# ADC.net
KiCad netlist of a schematic drawn in Altium Designer
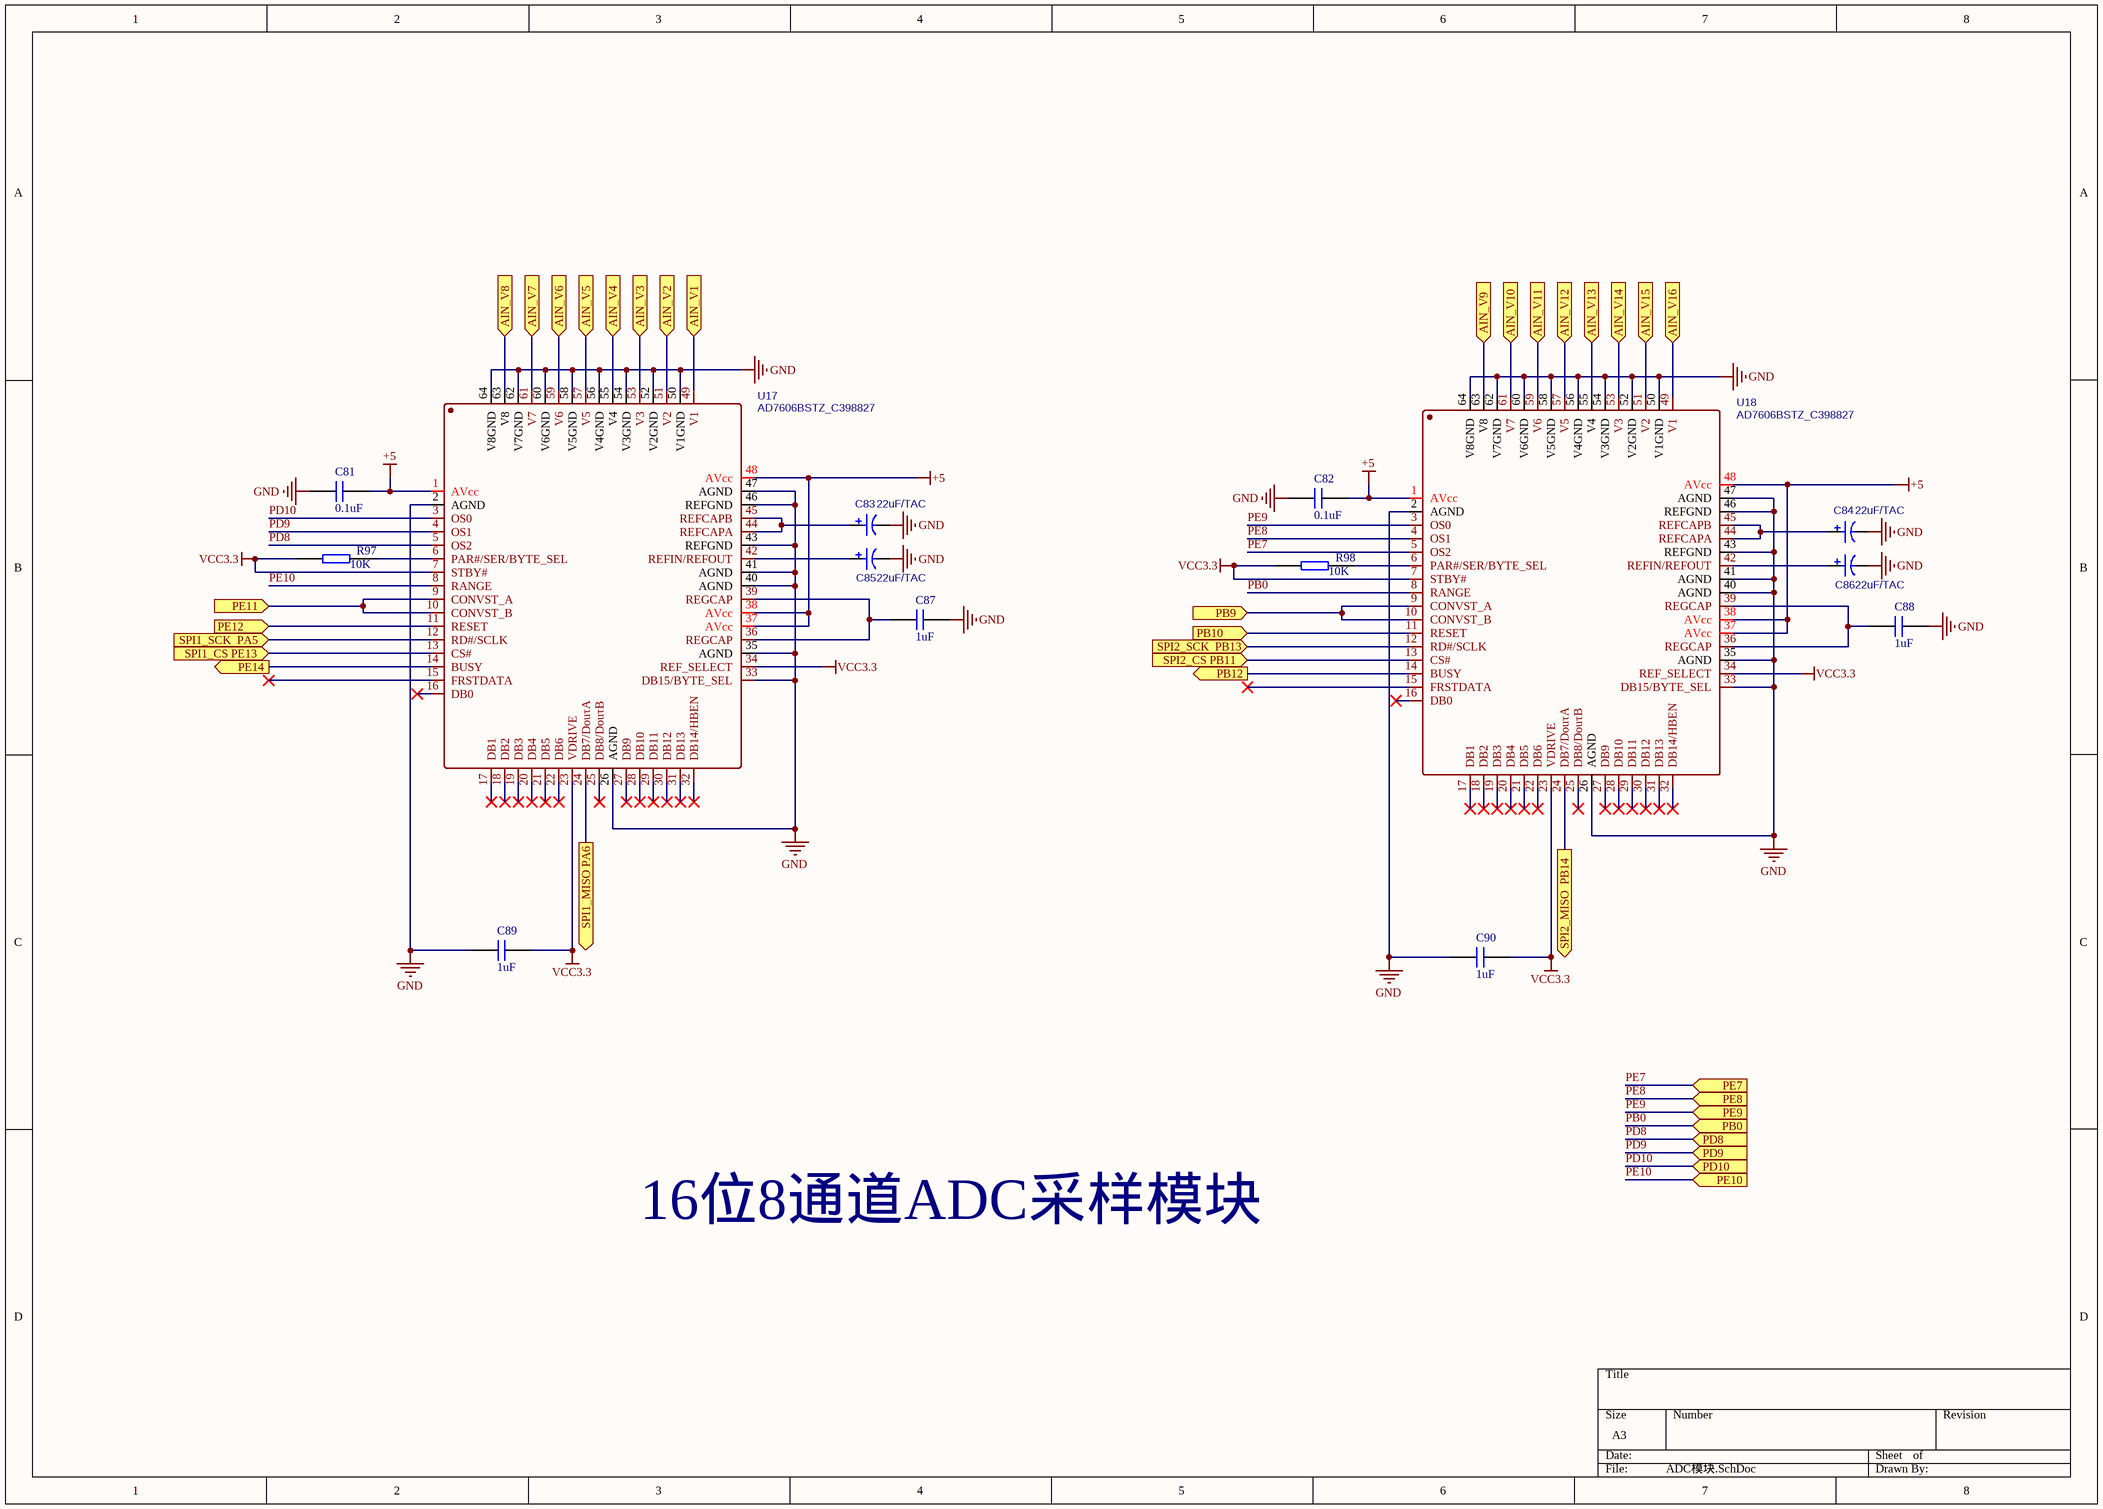
[diagram p0: ADC模块.SchDoc]

(export (version "E")
  (design (tool "Eeschema 10.0.6"))
  (components
    (comp (ref "C81")
      (value "0.1uF")
      (footprint "0805C")
      (description "普通电容")
      (libsource (lib "毕业设计") (part "CAP"))
    )
    (comp (ref "C82")
      (value "0.1uF")
      (footprint "0805C")
      (description "普通电容")
      (libsource (lib "毕业设计") (part "CAP"))
    )
    (comp (ref "C83")
      (value "22uF/TAC")
      (footprint "CASE-C_6032")
      (description "极性电解电容")
      (fields
        (field (name "BOM_MANUFACTURER PART") "Non - polar electrolytic capacitors10uf 100v")
        (field (name "BOM_SUPPLIER PART") "C56706")
      )
      (libsource (lib "毕业设计") (part "10uF"))
    )
    (comp (ref "C84")
      (value "22uF/TAC")
      (footprint "CASE-C_6032")
      (description "极性电解电容")
      (fields
        (field (name "BOM_MANUFACTURER PART") "Non - polar electrolytic capacitors10uf 100v")
        (field (name "BOM_SUPPLIER PART") "C56706")
      )
      (libsource (lib "毕业设计") (part "10uF"))
    )
    (comp (ref "C85")
      (value "22uF/TAC")
      (footprint "CASE-C_6032")
      (description "极性电解电容")
      (fields
        (field (name "BOM_MANUFACTURER PART") "Non - polar electrolytic capacitors10uf 100v")
        (field (name "BOM_SUPPLIER PART") "C56706")
      )
      (libsource (lib "毕业设计") (part "10uF"))
    )
    (comp (ref "C86")
      (value "22uF/TAC")
      (footprint "CASE-C_6032")
      (description "极性电解电容")
      (fields
        (field (name "BOM_MANUFACTURER PART") "Non - polar electrolytic capacitors10uf 100v")
        (field (name "BOM_SUPPLIER PART") "C56706")
      )
      (libsource (lib "毕业设计") (part "10uF"))
    )
    (comp (ref "C87")
      (value "1uF")
      (footprint "0805C")
      (description "普通电容")
      (libsource (lib "毕业设计") (part "CAP"))
    )
    (comp (ref "C88")
      (value "1uF")
      (footprint "0805C")
      (description "普通电容")
      (libsource (lib "毕业设计") (part "CAP"))
    )
    (comp (ref "C89")
      (value "1uF")
      (footprint "0805C")
      (description "普通电容")
      (libsource (lib "毕业设计") (part "CAP"))
    )
    (comp (ref "C90")
      (value "1uF")
      (footprint "0805C")
      (description "普通电容")
      (libsource (lib "毕业设计") (part "CAP"))
    )
    (comp (ref "R97")
      (value "10K")
      (footprint "0603R")
      (description "电阻模型")
      (libsource (lib "毕业设计") (part "RES"))
    )
    (comp (ref "R98")
      (value "10K")
      (footprint "0603R")
      (description "电阻模型")
      (libsource (lib "毕业设计") (part "RES"))
    )
    (comp (ref "U17")
      (value "AD7606BSTZ_C398827")
      (footprint "LQFP-64")
      (description "16位8路通道ADC")
      (fields
        (field (name "BOM_SUPPLIER PART") "C398827")
        (field (name "BOM_MANUFACTURER PART") "AD7606BSTZ")
        (field (name "CONTRIBUTOR") "LCSC")
      )
      (libsource (lib "毕业设计") (part "AD7606BSTZ_C398827"))
    )
    (comp (ref "U18")
      (value "AD7606BSTZ_C398827")
      (footprint "LQFP-64")
      (description "16位8路通道ADC")
      (fields
        (field (name "BOM_SUPPLIER PART") "C398827")
        (field (name "BOM_MANUFACTURER PART") "AD7606BSTZ")
        (field (name "CONTRIBUTOR") "LCSC")
      )
      (libsource (lib "毕业设计") (part "AD7606BSTZ_C398827"))
    )
  )
  (nets
    (net (code "1") (name "+5") (class "Default")
      (node (ref "C81") (pin "2") (pinfunction "2_2") (pintype "passive"))
      (node (ref "C82") (pin "2") (pinfunction "2_2") (pintype "passive"))
      (node (ref "U17") (pin "1") (pinfunction "AVcc_1") (pintype "passive"))
      (node (ref "U17") (pin "37") (pinfunction "AVcc_37") (pintype "passive"))
      (node (ref "U17") (pin "38") (pinfunction "AVcc_38") (pintype "passive"))
      (node (ref "U17") (pin "48") (pinfunction "AVcc_48") (pintype "passive"))
      (node (ref "U18") (pin "1") (pinfunction "AVcc_1") (pintype "passive"))
      (node (ref "U18") (pin "37") (pinfunction "AVcc_37") (pintype "passive"))
      (node (ref "U18") (pin "38") (pinfunction "AVcc_38") (pintype "passive"))
      (node (ref "U18") (pin "48") (pinfunction "AVcc_48") (pintype "passive"))
    )
    (net (code "2") (name "/AIN_V1") (class "Default")
      (node (ref "U17") (pin "49") (pinfunction "V1_49") (pintype "passive"))
    )
    (net (code "3") (name "/AIN_V2") (class "Default")
      (node (ref "U17") (pin "51") (pinfunction "V2_51") (pintype "passive"))
    )
    (net (code "4") (name "/AIN_V3") (class "Default")
      (node (ref "U17") (pin "53") (pinfunction "V3_53") (pintype "passive"))
    )
    (net (code "5") (name "/AIN_V4") (class "Default")
      (node (ref "U17") (pin "55") (pinfunction "V4_55") (pintype "passive"))
    )
    (net (code "6") (name "/AIN_V5") (class "Default")
      (node (ref "U17") (pin "57") (pinfunction "V5_57") (pintype "passive"))
    )
    (net (code "7") (name "/AIN_V6") (class "Default")
      (node (ref "U17") (pin "59") (pinfunction "V6_59") (pintype "passive"))
    )
    (net (code "8") (name "/AIN_V7") (class "Default")
      (node (ref "U17") (pin "61") (pinfunction "V7_61") (pintype "passive"))
    )
    (net (code "9") (name "/AIN_V8") (class "Default")
      (node (ref "U17") (pin "63") (pinfunction "V8_63") (pintype "passive"))
    )
    (net (code "10") (name "/AIN_V9") (class "Default")
      (node (ref "U18") (pin "63") (pinfunction "V8_63") (pintype "passive"))
    )
    (net (code "11") (name "/AIN_V10") (class "Default")
      (node (ref "U18") (pin "61") (pinfunction "V7_61") (pintype "passive"))
    )
    (net (code "12") (name "/AIN_V11") (class "Default")
      (node (ref "U18") (pin "59") (pinfunction "V6_59") (pintype "passive"))
    )
    (net (code "13") (name "/AIN_V12") (class "Default")
      (node (ref "U18") (pin "57") (pinfunction "V5_57") (pintype "passive"))
    )
    (net (code "14") (name "/AIN_V13") (class "Default")
      (node (ref "U18") (pin "55") (pinfunction "V4_55") (pintype "passive"))
    )
    (net (code "15") (name "/AIN_V14") (class "Default")
      (node (ref "U18") (pin "53") (pinfunction "V3_53") (pintype "passive"))
    )
    (net (code "16") (name "/AIN_V15") (class "Default")
      (node (ref "U18") (pin "51") (pinfunction "V2_51") (pintype "passive"))
    )
    (net (code "17") (name "/AIN_V16") (class "Default")
      (node (ref "U18") (pin "49") (pinfunction "V1_49") (pintype "passive"))
    )
    (net (code "18") (name "/PB0") (class "Default")
      (node (ref "U18") (pin "8") (pinfunction "RANGE_8") (pintype "passive"))
    )
    (net (code "19") (name "/PB9") (class "Default")
      (node (ref "U18") (pin "10") (pinfunction "CONVST_B_10") (pintype "passive"))
      (node (ref "U18") (pin "9") (pinfunction "CONVST_A_9") (pintype "passive"))
    )
    (net (code "20") (name "/PB10") (class "Default")
      (node (ref "U18") (pin "11") (pinfunction "RESET_11") (pintype "passive"))
    )
    (net (code "21") (name "/PB12") (class "Default")
      (node (ref "U18") (pin "14") (pinfunction "BUSY_14") (pintype "passive"))
    )
    (net (code "22") (name "/PD8") (class "Default")
      (node (ref "U17") (pin "5") (pinfunction "OS2_5") (pintype "passive"))
    )
    (net (code "23") (name "/PD9") (class "Default")
      (node (ref "U17") (pin "4") (pinfunction "OS1_4") (pintype "passive"))
    )
    (net (code "24") (name "/PD10") (class "Default")
      (node (ref "U17") (pin "3") (pinfunction "OS0_3") (pintype "passive"))
    )
    (net (code "25") (name "/PE7") (class "Default")
      (node (ref "U18") (pin "5") (pinfunction "OS2_5") (pintype "passive"))
    )
    (net (code "26") (name "/PE8") (class "Default")
      (node (ref "U18") (pin "4") (pinfunction "OS1_4") (pintype "passive"))
    )
    (net (code "27") (name "/PE9") (class "Default")
      (node (ref "U18") (pin "3") (pinfunction "OS0_3") (pintype "passive"))
    )
    (net (code "28") (name "/PE10") (class "Default")
      (node (ref "U17") (pin "8") (pinfunction "RANGE_8") (pintype "passive"))
    )
    (net (code "29") (name "/PE11") (class "Default")
      (node (ref "U17") (pin "10") (pinfunction "CONVST_B_10") (pintype "passive"))
      (node (ref "U17") (pin "9") (pinfunction "CONVST_A_9") (pintype "passive"))
    )
    (net (code "30") (name "/PE12") (class "Default")
      (node (ref "U17") (pin "11") (pinfunction "RESET_11") (pintype "passive"))
    )
    (net (code "31") (name "/PE14") (class "Default")
      (node (ref "U17") (pin "14") (pinfunction "BUSY_14") (pintype "passive"))
    )
    (net (code "32") (name "/SPI1_CS PE13") (class "Default")
      (node (ref "U17") (pin "13") (pinfunction "CS#_13") (pintype "passive"))
    )
    (net (code "33") (name "/SPI1_MISO PA6") (class "Default")
      (node (ref "U17") (pin "24") (pinfunction "DB7/DouτA_24") (pintype "passive"))
    )
    (net (code "34") (name "/SPI1_SCK  PA5") (class "Default")
      (node (ref "U17") (pin "12") (pinfunction "RD#/SCLK_12") (pintype "passive"))
    )
    (net (code "35") (name "/SPI2_CS PB11") (class "Default")
      (node (ref "U18") (pin "13") (pinfunction "CS#_13") (pintype "passive"))
    )
    (net (code "36") (name "/SPI2_MISO  PB14") (class "Default")
      (node (ref "U18") (pin "24") (pinfunction "DB7/DouτA_24") (pintype "passive"))
    )
    (net (code "37") (name "/SPI2_SCK  PB13") (class "Default")
      (node (ref "U18") (pin "12") (pinfunction "RD#/SCLK_12") (pintype "passive"))
    )
    (net (code "38") (name "GND") (class "Default")
      (node (ref "C81") (pin "1") (pinfunction "1_1") (pintype "passive"))
      (node (ref "C82") (pin "1") (pinfunction "1_1") (pintype "passive"))
      (node (ref "C83") (pin "2") (pinfunction "2_2") (pintype "passive"))
      (node (ref "C84") (pin "2") (pinfunction "2_2") (pintype "passive"))
      (node (ref "C85") (pin "2") (pinfunction "2_2") (pintype "passive"))
      (node (ref "C86") (pin "2") (pinfunction "2_2") (pintype "passive"))
      (node (ref "C87") (pin "2") (pinfunction "2_2") (pintype "passive"))
      (node (ref "C88") (pin "2") (pinfunction "2_2") (pintype "passive"))
      (node (ref "C89") (pin "1") (pinfunction "1_1") (pintype "passive"))
      (node (ref "C90") (pin "1") (pinfunction "1_1") (pintype "passive"))
      (node (ref "U17") (pin "2") (pinfunction "AGND_2") (pintype "passive"))
      (node (ref "U17") (pin "26") (pinfunction "AGND_26") (pintype "passive"))
      (node (ref "U17") (pin "33") (pinfunction "DB15/BYTE_SEL_33") (pintype "passive"))
      (node (ref "U17") (pin "35") (pinfunction "AGND_35") (pintype "passive"))
      (node (ref "U17") (pin "40") (pinfunction "AGND_40") (pintype "passive"))
      (node (ref "U17") (pin "41") (pinfunction "AGND_41") (pintype "passive"))
      (node (ref "U17") (pin "43") (pinfunction "REFGND_43") (pintype "passive"))
      (node (ref "U17") (pin "46") (pinfunction "REFGND_46") (pintype "passive"))
      (node (ref "U17") (pin "47") (pinfunction "AGND_47") (pintype "passive"))
      (node (ref "U17") (pin "50") (pinfunction "V1GND_50") (pintype "passive"))
      (node (ref "U17") (pin "52") (pinfunction "V2GND_52") (pintype "passive"))
      (node (ref "U17") (pin "54") (pinfunction "V3GND_54") (pintype "passive"))
      (node (ref "U17") (pin "56") (pinfunction "V4GND_56") (pintype "passive"))
      (node (ref "U17") (pin "58") (pinfunction "V5GND_58") (pintype "passive"))
      (node (ref "U17") (pin "60") (pinfunction "V6GND_60") (pintype "passive"))
      (node (ref "U17") (pin "62") (pinfunction "V7GND_62") (pintype "passive"))
      (node (ref "U17") (pin "64") (pinfunction "V8GND_64") (pintype "passive"))
      (node (ref "U18") (pin "2") (pinfunction "AGND_2") (pintype "passive"))
      (node (ref "U18") (pin "26") (pinfunction "AGND_26") (pintype "passive"))
      (node (ref "U18") (pin "33") (pinfunction "DB15/BYTE_SEL_33") (pintype "passive"))
      (node (ref "U18") (pin "35") (pinfunction "AGND_35") (pintype "passive"))
      (node (ref "U18") (pin "40") (pinfunction "AGND_40") (pintype "passive"))
      (node (ref "U18") (pin "41") (pinfunction "AGND_41") (pintype "passive"))
      (node (ref "U18") (pin "43") (pinfunction "REFGND_43") (pintype "passive"))
      (node (ref "U18") (pin "46") (pinfunction "REFGND_46") (pintype "passive"))
      (node (ref "U18") (pin "47") (pinfunction "AGND_47") (pintype "passive"))
      (node (ref "U18") (pin "50") (pinfunction "V1GND_50") (pintype "passive"))
      (node (ref "U18") (pin "52") (pinfunction "V2GND_52") (pintype "passive"))
      (node (ref "U18") (pin "54") (pinfunction "V3GND_54") (pintype "passive"))
      (node (ref "U18") (pin "56") (pinfunction "V4GND_56") (pintype "passive"))
      (node (ref "U18") (pin "58") (pinfunction "V5GND_58") (pintype "passive"))
      (node (ref "U18") (pin "60") (pinfunction "V6GND_60") (pintype "passive"))
      (node (ref "U18") (pin "62") (pinfunction "V7GND_62") (pintype "passive"))
      (node (ref "U18") (pin "64") (pinfunction "V8GND_64") (pintype "passive"))
    )
    (net (code "39") (name "Net-(C87-Pad1)") (class "Default")
      (node (ref "C87") (pin "1") (pinfunction "1_1") (pintype "passive"))
      (node (ref "U17") (pin "36") (pinfunction "REGCAP_36") (pintype "passive"))
      (node (ref "U17") (pin "39") (pinfunction "REGCAP_39") (pintype "passive"))
    )
    (net (code "40") (name "Net-(C88-Pad1)") (class "Default")
      (node (ref "C88") (pin "1") (pinfunction "1_1") (pintype "passive"))
      (node (ref "U18") (pin "36") (pinfunction "REGCAP_36") (pintype "passive"))
      (node (ref "U18") (pin "39") (pinfunction "REGCAP_39") (pintype "passive"))
    )
    (net (code "41") (name "Net-(U17-PAR#{slash}SER{slash}BYTE_SEL)") (class "Default")
      (node (ref "R97") (pin "2") (pinfunction "2_2") (pintype "passive"))
      (node (ref "U17") (pin "6") (pinfunction "PAR#/SER/BYTE_SEL_6") (pintype "passive"))
    )
    (net (code "42") (name "Net-(U17-REFCAPA)") (class "Default")
      (node (ref "C83") (pin "1") (pinfunction "1_1") (pintype "passive"))
      (node (ref "U17") (pin "44") (pinfunction "REFCAPA_44") (pintype "passive"))
      (node (ref "U17") (pin "45") (pinfunction "REFCAPB_45") (pintype "passive"))
    )
    (net (code "43") (name "Net-(U17-REFIN{slash}REFOUT)") (class "Default")
      (node (ref "C85") (pin "1") (pinfunction "1_1") (pintype "passive"))
      (node (ref "U17") (pin "42") (pinfunction "REFIN/REFOUT_42") (pintype "passive"))
    )
    (net (code "44") (name "Net-(U18-PAR#{slash}SER{slash}BYTE_SEL)") (class "Default")
      (node (ref "R98") (pin "2") (pinfunction "2_2") (pintype "passive"))
      (node (ref "U18") (pin "6") (pinfunction "PAR#/SER/BYTE_SEL_6") (pintype "passive"))
    )
    (net (code "45") (name "Net-(U18-REFCAPA)") (class "Default")
      (node (ref "C84") (pin "1") (pinfunction "1_1") (pintype "passive"))
      (node (ref "U18") (pin "44") (pinfunction "REFCAPA_44") (pintype "passive"))
      (node (ref "U18") (pin "45") (pinfunction "REFCAPB_45") (pintype "passive"))
    )
    (net (code "46") (name "Net-(U18-REFIN{slash}REFOUT)") (class "Default")
      (node (ref "C86") (pin "1") (pinfunction "1_1") (pintype "passive"))
      (node (ref "U18") (pin "42") (pinfunction "REFIN/REFOUT_42") (pintype "passive"))
    )
    (net (code "47") (name "VCC3.3") (class "Default")
      (node (ref "C89") (pin "2") (pinfunction "2_2") (pintype "passive"))
      (node (ref "C90") (pin "2") (pinfunction "2_2") (pintype "passive"))
      (node (ref "R97") (pin "1") (pinfunction "1_1") (pintype "passive"))
      (node (ref "R98") (pin "1") (pinfunction "1_1") (pintype "passive"))
      (node (ref "U17") (pin "23") (pinfunction "VDRIVE_23") (pintype "passive"))
      (node (ref "U17") (pin "34") (pinfunction "REF_SELECT_34") (pintype "passive"))
      (node (ref "U17") (pin "7") (pinfunction "STBY#_7") (pintype "passive"))
      (node (ref "U18") (pin "23") (pinfunction "VDRIVE_23") (pintype "passive"))
      (node (ref "U18") (pin "34") (pinfunction "REF_SELECT_34") (pintype "passive"))
      (node (ref "U18") (pin "7") (pinfunction "STBY#_7") (pintype "passive"))
    )
    (net (code "48") (name "unconnected-(U17-DB0-Pad16)") (class "Default")
      (node (ref "U17") (pin "16") (pinfunction "DB0_16") (pintype "passive+no_connect"))
    )
    (net (code "49") (name "unconnected-(U17-DB1-Pad17)") (class "Default")
      (node (ref "U17") (pin "17") (pinfunction "DB1_17") (pintype "passive+no_connect"))
    )
    (net (code "50") (name "unconnected-(U17-DB2-Pad18)") (class "Default")
      (node (ref "U17") (pin "18") (pinfunction "DB2_18") (pintype "passive+no_connect"))
    )
    (net (code "51") (name "unconnected-(U17-DB3-Pad19)") (class "Default")
      (node (ref "U17") (pin "19") (pinfunction "DB3_19") (pintype "passive+no_connect"))
    )
    (net (code "52") (name "unconnected-(U17-DB4-Pad20)") (class "Default")
      (node (ref "U17") (pin "20") (pinfunction "DB4_20") (pintype "passive+no_connect"))
    )
    (net (code "53") (name "unconnected-(U17-DB5-Pad21)") (class "Default")
      (node (ref "U17") (pin "21") (pinfunction "DB5_21") (pintype "passive+no_connect"))
    )
    (net (code "54") (name "unconnected-(U17-DB6-Pad22)") (class "Default")
      (node (ref "U17") (pin "22") (pinfunction "DB6_22") (pintype "passive+no_connect"))
    )
    (net (code "55") (name "unconnected-(U17-DB8{slash}DouτB-Pad25)") (class "Default")
      (node (ref "U17") (pin "25") (pinfunction "DB8/DouτB_25") (pintype "passive+no_connect"))
    )
    (net (code "56") (name "unconnected-(U17-DB9-Pad27)") (class "Default")
      (node (ref "U17") (pin "27") (pinfunction "DB9_27") (pintype "passive+no_connect"))
    )
    (net (code "57") (name "unconnected-(U17-DB10-Pad28)") (class "Default")
      (node (ref "U17") (pin "28") (pinfunction "DB10_28") (pintype "passive+no_connect"))
    )
    (net (code "58") (name "unconnected-(U17-DB11-Pad29)") (class "Default")
      (node (ref "U17") (pin "29") (pinfunction "DB11_29") (pintype "passive+no_connect"))
    )
    (net (code "59") (name "unconnected-(U17-DB12-Pad30)") (class "Default")
      (node (ref "U17") (pin "30") (pinfunction "DB12_30") (pintype "passive+no_connect"))
    )
    (net (code "60") (name "unconnected-(U17-DB13-Pad31)") (class "Default")
      (node (ref "U17") (pin "31") (pinfunction "DB13_31") (pintype "passive+no_connect"))
    )
    (net (code "61") (name "unconnected-(U17-DB14{slash}HBEN-Pad32)") (class "Default")
      (node (ref "U17") (pin "32") (pinfunction "DB14/HBEN_32") (pintype "passive+no_connect"))
    )
    (net (code "62") (name "unconnected-(U17-FRSTDATA-Pad15)") (class "Default")
      (node (ref "U17") (pin "15") (pinfunction "FRSTDATA_15") (pintype "passive+no_connect"))
    )
    (net (code "63") (name "unconnected-(U18-DB0-Pad16)") (class "Default")
      (node (ref "U18") (pin "16") (pinfunction "DB0_16") (pintype "passive+no_connect"))
    )
    (net (code "64") (name "unconnected-(U18-DB1-Pad17)") (class "Default")
      (node (ref "U18") (pin "17") (pinfunction "DB1_17") (pintype "passive+no_connect"))
    )
    (net (code "65") (name "unconnected-(U18-DB2-Pad18)") (class "Default")
      (node (ref "U18") (pin "18") (pinfunction "DB2_18") (pintype "passive+no_connect"))
    )
    (net (code "66") (name "unconnected-(U18-DB3-Pad19)") (class "Default")
      (node (ref "U18") (pin "19") (pinfunction "DB3_19") (pintype "passive+no_connect"))
    )
    (net (code "67") (name "unconnected-(U18-DB4-Pad20)") (class "Default")
      (node (ref "U18") (pin "20") (pinfunction "DB4_20") (pintype "passive+no_connect"))
    )
    (net (code "68") (name "unconnected-(U18-DB5-Pad21)") (class "Default")
      (node (ref "U18") (pin "21") (pinfunction "DB5_21") (pintype "passive+no_connect"))
    )
    (net (code "69") (name "unconnected-(U18-DB6-Pad22)") (class "Default")
      (node (ref "U18") (pin "22") (pinfunction "DB6_22") (pintype "passive+no_connect"))
    )
    (net (code "70") (name "unconnected-(U18-DB8{slash}DouτB-Pad25)") (class "Default")
      (node (ref "U18") (pin "25") (pinfunction "DB8/DouτB_25") (pintype "passive+no_connect"))
    )
    (net (code "71") (name "unconnected-(U18-DB9-Pad27)") (class "Default")
      (node (ref "U18") (pin "27") (pinfunction "DB9_27") (pintype "passive+no_connect"))
    )
    (net (code "72") (name "unconnected-(U18-DB10-Pad28)") (class "Default")
      (node (ref "U18") (pin "28") (pinfunction "DB10_28") (pintype "passive+no_connect"))
    )
    (net (code "73") (name "unconnected-(U18-DB11-Pad29)") (class "Default")
      (node (ref "U18") (pin "29") (pinfunction "DB11_29") (pintype "passive+no_connect"))
    )
    (net (code "74") (name "unconnected-(U18-DB12-Pad30)") (class "Default")
      (node (ref "U18") (pin "30") (pinfunction "DB12_30") (pintype "passive+no_connect"))
    )
    (net (code "75") (name "unconnected-(U18-DB13-Pad31)") (class "Default")
      (node (ref "U18") (pin "31") (pinfunction "DB13_31") (pintype "passive+no_connect"))
    )
    (net (code "76") (name "unconnected-(U18-DB14{slash}HBEN-Pad32)") (class "Default")
      (node (ref "U18") (pin "32") (pinfunction "DB14/HBEN_32") (pintype "passive+no_connect"))
    )
    (net (code "77") (name "unconnected-(U18-FRSTDATA-Pad15)") (class "Default")
      (node (ref "U18") (pin "15") (pinfunction "FRSTDATA_15") (pintype "passive+no_connect"))
    )
  )
)
